# channel_2.net
KiCad netlist of a schematic drawn in Altium Designer
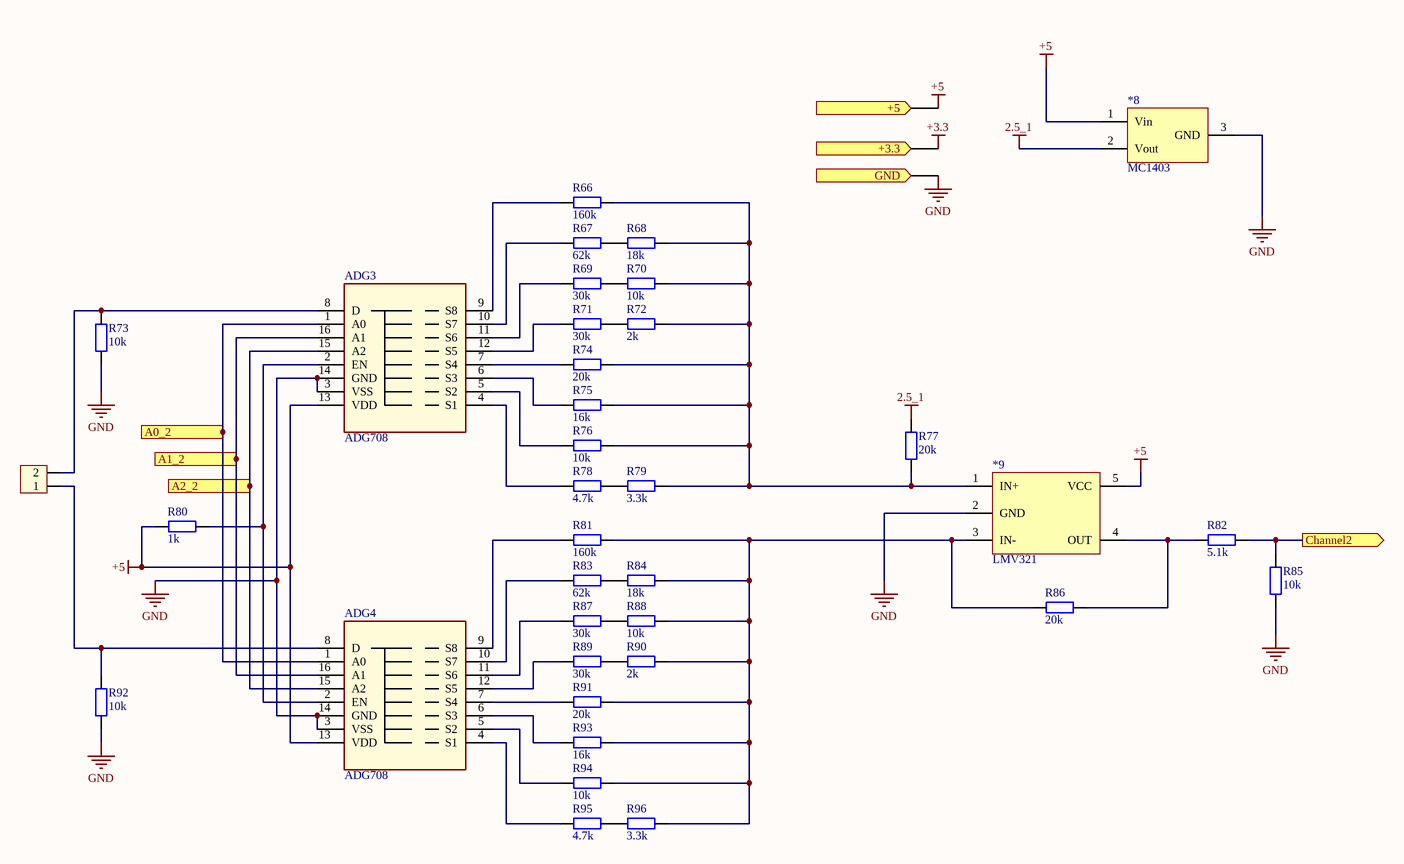
[diagram p0: channel_2.SchDoc]

(export (version "E")
  (design (tool "Eeschema 10.0.6"))
  (components
    (comp (ref "*8") (value "MC1403") (footprint "dip8") (libsource (lib "TrungVan_Lib") (part "MC1403")))
    (comp (ref "*9") (value "LMV321") (footprint "SOT23-5") (libsource (lib "TrungVan_Lib") (part "LMV321")))
    (comp (ref "ADG3")
      (value "ADG708")
      (footprint "TSSOP16")
      (libsource (lib "TrungVan_Lib") (part "ADG708"))
    )
    (comp (ref "ADG4")
      (value "ADG708")
      (footprint "TSSOP16")
      (libsource (lib "TrungVan_Lib") (part "ADG708"))
    )
    (comp (ref "H2")
      (value "Header 2P 2.54 Duc Thang")
      (footprint "15EDGR-3.81-2P")
      (description "Cắm")
      (libsource (lib "TrungVan_Lib") (part "Header 2P 2.54 Duc Thang"))
    )
    (comp (ref "R66")
      (value "160k")
      (footprint "tro smd 0603")
      (description "Dán")
      (libsource (lib "TrungVan_Lib") (part "Tro 2512 5% 100k"))
    )
    (comp (ref "R67")
      (value "62k")
      (footprint "tro smd 0603")
      (description "Dán")
      (libsource (lib "TrungVan_Lib") (part "Tro 2512 5% 100k"))
    )
    (comp (ref "R68")
      (value "18k")
      (footprint "tro smd 0603")
      (description "Dán")
      (libsource (lib "TrungVan_Lib") (part "Tro 2512 5% 100k"))
    )
    (comp (ref "R69")
      (value "30k")
      (footprint "tro smd 0603")
      (description "Dán")
      (libsource (lib "TrungVan_Lib") (part "Tro 2512 5% 100k"))
    )
    (comp (ref "R70")
      (value "10k")
      (footprint "tro smd 0603")
      (description "Dán")
      (libsource (lib "TrungVan_Lib") (part "Tro 2512 5% 100k"))
    )
    (comp (ref "R71")
      (value "30k")
      (footprint "tro smd 0603")
      (description "Dán")
      (libsource (lib "TrungVan_Lib") (part "Tro 2512 5% 100k"))
    )
    (comp (ref "R72")
      (value "2k")
      (footprint "tro smd 0603")
      (description "Dán")
      (libsource (lib "TrungVan_Lib") (part "Tro 2512 5% 100k"))
    )
    (comp (ref "R73")
      (value "10k")
      (footprint "tro smd 0603")
      (description "Dán")
      (libsource (lib "TrungVan_Lib") (part "Tro 2512 5% 100k"))
    )
    (comp (ref "R74")
      (value "20k")
      (footprint "tro smd 0603")
      (description "Dán")
      (libsource (lib "TrungVan_Lib") (part "Tro 2512 5% 100k"))
    )
    (comp (ref "R75")
      (value "16k")
      (footprint "tro smd 0603")
      (description "Dán")
      (libsource (lib "TrungVan_Lib") (part "Tro 2512 5% 100k"))
    )
    (comp (ref "R76")
      (value "10k")
      (footprint "tro smd 0603")
      (description "Dán")
      (libsource (lib "TrungVan_Lib") (part "Tro 2512 5% 100k"))
    )
    (comp (ref "R77")
      (value "20k")
      (footprint "tro smd 0603")
      (description "Dán")
      (libsource (lib "TrungVan_Lib") (part "Tro 2512 5% 100k"))
    )
    (comp (ref "R78")
      (value "4.7k")
      (footprint "tro smd 0603")
      (description "Dán")
      (libsource (lib "TrungVan_Lib") (part "Tro 2512 5% 100k"))
    )
    (comp (ref "R79")
      (value "3.3k")
      (footprint "tro smd 0603")
      (description "Dán")
      (libsource (lib "TrungVan_Lib") (part "Tro 2512 5% 100k"))
    )
    (comp (ref "R80")
      (value "1k")
      (footprint "tro smd 0603")
      (description "Dán")
      (libsource (lib "TrungVan_Lib") (part "Tro 2512 5% 100k"))
    )
    (comp (ref "R81")
      (value "160k")
      (footprint "tro smd 0603")
      (description "Dán")
      (libsource (lib "TrungVan_Lib") (part "Tro 2512 5% 100k"))
    )
    (comp (ref "R82")
      (value "5.1k")
      (footprint "tro smd 0603")
      (description "Dán")
      (libsource (lib "TrungVan_Lib") (part "Tro 0603 1% 10k"))
    )
    (comp (ref "R83")
      (value "62k")
      (footprint "tro smd 0603")
      (description "Dán")
      (libsource (lib "TrungVan_Lib") (part "Tro 2512 5% 100k"))
    )
    (comp (ref "R84")
      (value "18k")
      (footprint "tro smd 0603")
      (description "Dán")
      (libsource (lib "TrungVan_Lib") (part "Tro 2512 5% 100k"))
    )
    (comp (ref "R85")
      (value "10k")
      (footprint "tro smd 0603")
      (description "Dán")
      (libsource (lib "TrungVan_Lib") (part "Tro 0603 1% 10k"))
    )
    (comp (ref "R86")
      (value "20k")
      (footprint "tro smd 0603")
      (description "Dán")
      (libsource (lib "TrungVan_Lib") (part "Tro 2512 5% 100k"))
    )
    (comp (ref "R87")
      (value "30k")
      (footprint "tro smd 0603")
      (description "Dán")
      (libsource (lib "TrungVan_Lib") (part "Tro 2512 5% 100k"))
    )
    (comp (ref "R88")
      (value "10k")
      (footprint "tro smd 0603")
      (description "Dán")
      (libsource (lib "TrungVan_Lib") (part "Tro 2512 5% 100k"))
    )
    (comp (ref "R89")
      (value "30k")
      (footprint "tro smd 0603")
      (description "Dán")
      (libsource (lib "TrungVan_Lib") (part "Tro 2512 5% 100k"))
    )
    (comp (ref "R90")
      (value "2k")
      (footprint "tro smd 0603")
      (description "Dán")
      (libsource (lib "TrungVan_Lib") (part "Tro 2512 5% 100k"))
    )
    (comp (ref "R91")
      (value "20k")
      (footprint "tro smd 0603")
      (description "Dán")
      (libsource (lib "TrungVan_Lib") (part "Tro 2512 5% 100k"))
    )
    (comp (ref "R92")
      (value "10k")
      (footprint "tro smd 0603")
      (description "Dán")
      (libsource (lib "TrungVan_Lib") (part "Tro 2512 5% 100k"))
    )
    (comp (ref "R93")
      (value "16k")
      (footprint "tro smd 0603")
      (description "Dán")
      (libsource (lib "TrungVan_Lib") (part "Tro 2512 5% 100k"))
    )
    (comp (ref "R94")
      (value "10k")
      (footprint "tro smd 0603")
      (description "Dán")
      (libsource (lib "TrungVan_Lib") (part "Tro 2512 5% 100k"))
    )
    (comp (ref "R95")
      (value "4.7k")
      (footprint "tro smd 0603")
      (description "Dán")
      (libsource (lib "TrungVan_Lib") (part "Tro 2512 5% 100k"))
    )
    (comp (ref "R96")
      (value "3.3k")
      (footprint "tro smd 0603")
      (description "Dán")
      (libsource (lib "TrungVan_Lib") (part "Tro 2512 5% 100k"))
    )
  )
  (nets
    (net (code "2") (name "+5") (class "Default")
      (node (ref "*8") (pin "1") (pinfunction "Vin_1") (pintype "passive"))
      (node (ref "*9") (pin "5") (pinfunction "VCC_5") (pintype "passive"))
      (node (ref "ADG3") (pin "13") (pinfunction "VDD_13") (pintype "passive"))
      (node (ref "ADG4") (pin "13") (pinfunction "VDD_13") (pintype "passive"))
      (node (ref "R80") (pin "2") (pinfunction "2_2") (pintype "passive"))
    )
    (net (code "3") (name "/A0_2") (class "Default")
      (node (ref "ADG3") (pin "1") (pinfunction "A0_1") (pintype "passive"))
      (node (ref "ADG4") (pin "1") (pinfunction "A0_1") (pintype "passive"))
    )
    (net (code "4") (name "/A1_2") (class "Default")
      (node (ref "ADG3") (pin "16") (pinfunction "A1_16") (pintype "passive"))
      (node (ref "ADG4") (pin "16") (pinfunction "A1_16") (pintype "passive"))
    )
    (net (code "5") (name "/A2_2") (class "Default")
      (node (ref "ADG3") (pin "15") (pinfunction "A2_15") (pintype "passive"))
      (node (ref "ADG4") (pin "15") (pinfunction "A2_15") (pintype "passive"))
    )
    (net (code "6") (name "/Channel2") (class "Default")
      (node (ref "R82") (pin "2") (pinfunction "2_2") (pintype "passive"))
      (node (ref "R85") (pin "2") (pinfunction "2_2") (pintype "passive"))
    )
    (net (code "7") (name "2.5_1") (class "Default")
      (node (ref "*8") (pin "2") (pinfunction "Vout_2") (pintype "passive"))
      (node (ref "R77") (pin "2") (pinfunction "2_2") (pintype "passive"))
    )
    (net (code "8") (name "GND") (class "Default")
      (node (ref "*8") (pin "3") (pinfunction "GND_3") (pintype "passive"))
      (node (ref "*9") (pin "2") (pinfunction "GND_2") (pintype "passive"))
      (node (ref "ADG3") (pin "14") (pinfunction "GND_14") (pintype "passive"))
      (node (ref "ADG3") (pin "3") (pinfunction "VSS_3") (pintype "passive"))
      (node (ref "ADG4") (pin "14") (pinfunction "GND_14") (pintype "passive"))
      (node (ref "ADG4") (pin "3") (pinfunction "VSS_3") (pintype "passive"))
      (node (ref "R73") (pin "2") (pinfunction "2_2") (pintype "passive"))
      (node (ref "R85") (pin "1") (pinfunction "1_1") (pintype "passive"))
      (node (ref "R92") (pin "2") (pinfunction "2_2") (pintype "passive"))
    )
    (net (code "9") (name "Net-(*9-IN+)") (class "Default")
      (node (ref "*9") (pin "1") (pinfunction "IN+_1") (pintype "passive"))
      (node (ref "R66") (pin "2") (pinfunction "2_2") (pintype "passive"))
      (node (ref "R68") (pin "2") (pinfunction "2_2") (pintype "passive"))
      (node (ref "R70") (pin "2") (pinfunction "2_2") (pintype "passive"))
      (node (ref "R72") (pin "2") (pinfunction "2_2") (pintype "passive"))
      (node (ref "R74") (pin "2") (pinfunction "2_2") (pintype "passive"))
      (node (ref "R75") (pin "2") (pinfunction "2_2") (pintype "passive"))
      (node (ref "R76") (pin "2") (pinfunction "2_2") (pintype "passive"))
      (node (ref "R77") (pin "1") (pinfunction "1_1") (pintype "passive"))
      (node (ref "R79") (pin "2") (pinfunction "2_2") (pintype "passive"))
    )
    (net (code "10") (name "Net-(*9-IN-)") (class "Default")
      (node (ref "*9") (pin "3") (pinfunction "IN-_3") (pintype "passive"))
      (node (ref "R81") (pin "2") (pinfunction "2_2") (pintype "passive"))
      (node (ref "R84") (pin "2") (pinfunction "2_2") (pintype "passive"))
      (node (ref "R86") (pin "1") (pinfunction "1_1") (pintype "passive"))
      (node (ref "R88") (pin "2") (pinfunction "2_2") (pintype "passive"))
      (node (ref "R90") (pin "2") (pinfunction "2_2") (pintype "passive"))
      (node (ref "R91") (pin "2") (pinfunction "2_2") (pintype "passive"))
      (node (ref "R93") (pin "2") (pinfunction "2_2") (pintype "passive"))
      (node (ref "R94") (pin "2") (pinfunction "2_2") (pintype "passive"))
      (node (ref "R96") (pin "2") (pinfunction "2_2") (pintype "passive"))
    )
    (net (code "11") (name "Net-(*9-OUT)") (class "Default")
      (node (ref "*9") (pin "4") (pinfunction "OUT_4") (pintype "passive"))
      (node (ref "R82") (pin "1") (pinfunction "1_1") (pintype "passive"))
      (node (ref "R86") (pin "2") (pinfunction "2_2") (pintype "passive"))
    )
    (net (code "12") (name "Net-(ADG3-D)") (class "Default")
      (node (ref "ADG3") (pin "8") (pinfunction "D_8") (pintype "passive"))
      (node (ref "H2") (pin "2") (pinfunction "2_2") (pintype "passive"))
      (node (ref "R73") (pin "1") (pinfunction "1_1") (pintype "passive"))
    )
    (net (code "13") (name "Net-(ADG3-EN)") (class "Default")
      (node (ref "ADG3") (pin "2") (pinfunction "EN_2") (pintype "passive"))
      (node (ref "ADG4") (pin "2") (pinfunction "EN_2") (pintype "passive"))
      (node (ref "R80") (pin "1") (pinfunction "1_1") (pintype "passive"))
    )
    (net (code "14") (name "Net-(ADG3-S1)") (class "Default")
      (node (ref "ADG3") (pin "4") (pinfunction "S1_4") (pintype "passive"))
      (node (ref "R78") (pin "1") (pinfunction "1_1") (pintype "passive"))
    )
    (net (code "15") (name "Net-(ADG3-S2)") (class "Default")
      (node (ref "ADG3") (pin "5") (pinfunction "S2_5") (pintype "passive"))
      (node (ref "R76") (pin "1") (pinfunction "1_1") (pintype "passive"))
    )
    (net (code "16") (name "Net-(ADG3-S3)") (class "Default")
      (node (ref "ADG3") (pin "6") (pinfunction "S3_6") (pintype "passive"))
      (node (ref "R75") (pin "1") (pinfunction "1_1") (pintype "passive"))
    )
    (net (code "17") (name "Net-(ADG3-S4)") (class "Default")
      (node (ref "ADG3") (pin "7") (pinfunction "S4_7") (pintype "passive"))
      (node (ref "R74") (pin "1") (pinfunction "1_1") (pintype "passive"))
    )
    (net (code "18") (name "Net-(ADG3-S5)") (class "Default")
      (node (ref "ADG3") (pin "12") (pinfunction "S5_12") (pintype "passive"))
      (node (ref "R71") (pin "1") (pinfunction "1_1") (pintype "passive"))
    )
    (net (code "19") (name "Net-(ADG3-S6)") (class "Default")
      (node (ref "ADG3") (pin "11") (pinfunction "S6_11") (pintype "passive"))
      (node (ref "R69") (pin "1") (pinfunction "1_1") (pintype "passive"))
    )
    (net (code "20") (name "Net-(ADG3-S7)") (class "Default")
      (node (ref "ADG3") (pin "10") (pinfunction "S7_10") (pintype "passive"))
      (node (ref "R67") (pin "1") (pinfunction "1_1") (pintype "passive"))
    )
    (net (code "21") (name "Net-(ADG3-S8)") (class "Default")
      (node (ref "ADG3") (pin "9") (pinfunction "S8_9") (pintype "passive"))
      (node (ref "R66") (pin "1") (pinfunction "1_1") (pintype "passive"))
    )
    (net (code "22") (name "Net-(ADG4-D)") (class "Default")
      (node (ref "ADG4") (pin "8") (pinfunction "D_8") (pintype "passive"))
      (node (ref "H2") (pin "1") (pinfunction "1_1") (pintype "passive"))
      (node (ref "R92") (pin "1") (pinfunction "1_1") (pintype "passive"))
    )
    (net (code "23") (name "Net-(ADG4-S1)") (class "Default")
      (node (ref "ADG4") (pin "4") (pinfunction "S1_4") (pintype "passive"))
      (node (ref "R95") (pin "1") (pinfunction "1_1") (pintype "passive"))
    )
    (net (code "24") (name "Net-(ADG4-S2)") (class "Default")
      (node (ref "ADG4") (pin "5") (pinfunction "S2_5") (pintype "passive"))
      (node (ref "R94") (pin "1") (pinfunction "1_1") (pintype "passive"))
    )
    (net (code "25") (name "Net-(ADG4-S3)") (class "Default")
      (node (ref "ADG4") (pin "6") (pinfunction "S3_6") (pintype "passive"))
      (node (ref "R93") (pin "1") (pinfunction "1_1") (pintype "passive"))
    )
    (net (code "26") (name "Net-(ADG4-S4)") (class "Default")
      (node (ref "ADG4") (pin "7") (pinfunction "S4_7") (pintype "passive"))
      (node (ref "R91") (pin "1") (pinfunction "1_1") (pintype "passive"))
    )
    (net (code "27") (name "Net-(ADG4-S5)") (class "Default")
      (node (ref "ADG4") (pin "12") (pinfunction "S5_12") (pintype "passive"))
      (node (ref "R89") (pin "1") (pinfunction "1_1") (pintype "passive"))
    )
    (net (code "28") (name "Net-(ADG4-S6)") (class "Default")
      (node (ref "ADG4") (pin "11") (pinfunction "S6_11") (pintype "passive"))
      (node (ref "R87") (pin "1") (pinfunction "1_1") (pintype "passive"))
    )
    (net (code "29") (name "Net-(ADG4-S7)") (class "Default")
      (node (ref "ADG4") (pin "10") (pinfunction "S7_10") (pintype "passive"))
      (node (ref "R83") (pin "1") (pinfunction "1_1") (pintype "passive"))
    )
    (net (code "30") (name "Net-(ADG4-S8)") (class "Default")
      (node (ref "ADG4") (pin "9") (pinfunction "S8_9") (pintype "passive"))
      (node (ref "R81") (pin "1") (pinfunction "1_1") (pintype "passive"))
    )
    (net (code "31") (name "Net-(R67-Pad2)") (class "Default")
      (node (ref "R67") (pin "2") (pinfunction "2_2") (pintype "passive"))
      (node (ref "R68") (pin "1") (pinfunction "1_1") (pintype "passive"))
    )
    (net (code "32") (name "Net-(R69-Pad2)") (class "Default")
      (node (ref "R69") (pin "2") (pinfunction "2_2") (pintype "passive"))
      (node (ref "R70") (pin "1") (pinfunction "1_1") (pintype "passive"))
    )
    (net (code "33") (name "Net-(R71-Pad2)") (class "Default")
      (node (ref "R71") (pin "2") (pinfunction "2_2") (pintype "passive"))
      (node (ref "R72") (pin "1") (pinfunction "1_1") (pintype "passive"))
    )
    (net (code "34") (name "Net-(R78-Pad2)") (class "Default")
      (node (ref "R78") (pin "2") (pinfunction "2_2") (pintype "passive"))
      (node (ref "R79") (pin "1") (pinfunction "1_1") (pintype "passive"))
    )
    (net (code "35") (name "Net-(R83-Pad2)") (class "Default")
      (node (ref "R83") (pin "2") (pinfunction "2_2") (pintype "passive"))
      (node (ref "R84") (pin "1") (pinfunction "1_1") (pintype "passive"))
    )
    (net (code "36") (name "Net-(R87-Pad2)") (class "Default")
      (node (ref "R87") (pin "2") (pinfunction "2_2") (pintype "passive"))
      (node (ref "R88") (pin "1") (pinfunction "1_1") (pintype "passive"))
    )
    (net (code "37") (name "Net-(R89-Pad2)") (class "Default")
      (node (ref "R89") (pin "2") (pinfunction "2_2") (pintype "passive"))
      (node (ref "R90") (pin "1") (pinfunction "1_1") (pintype "passive"))
    )
    (net (code "38") (name "Net-(R95-Pad2)") (class "Default")
      (node (ref "R95") (pin "2") (pinfunction "2_2") (pintype "passive"))
      (node (ref "R96") (pin "1") (pinfunction "1_1") (pintype "passive"))
    )
  )
)
